# SerialTrainSensor_drill.net
KiCad netlist of a schematic drawn in EAGLE
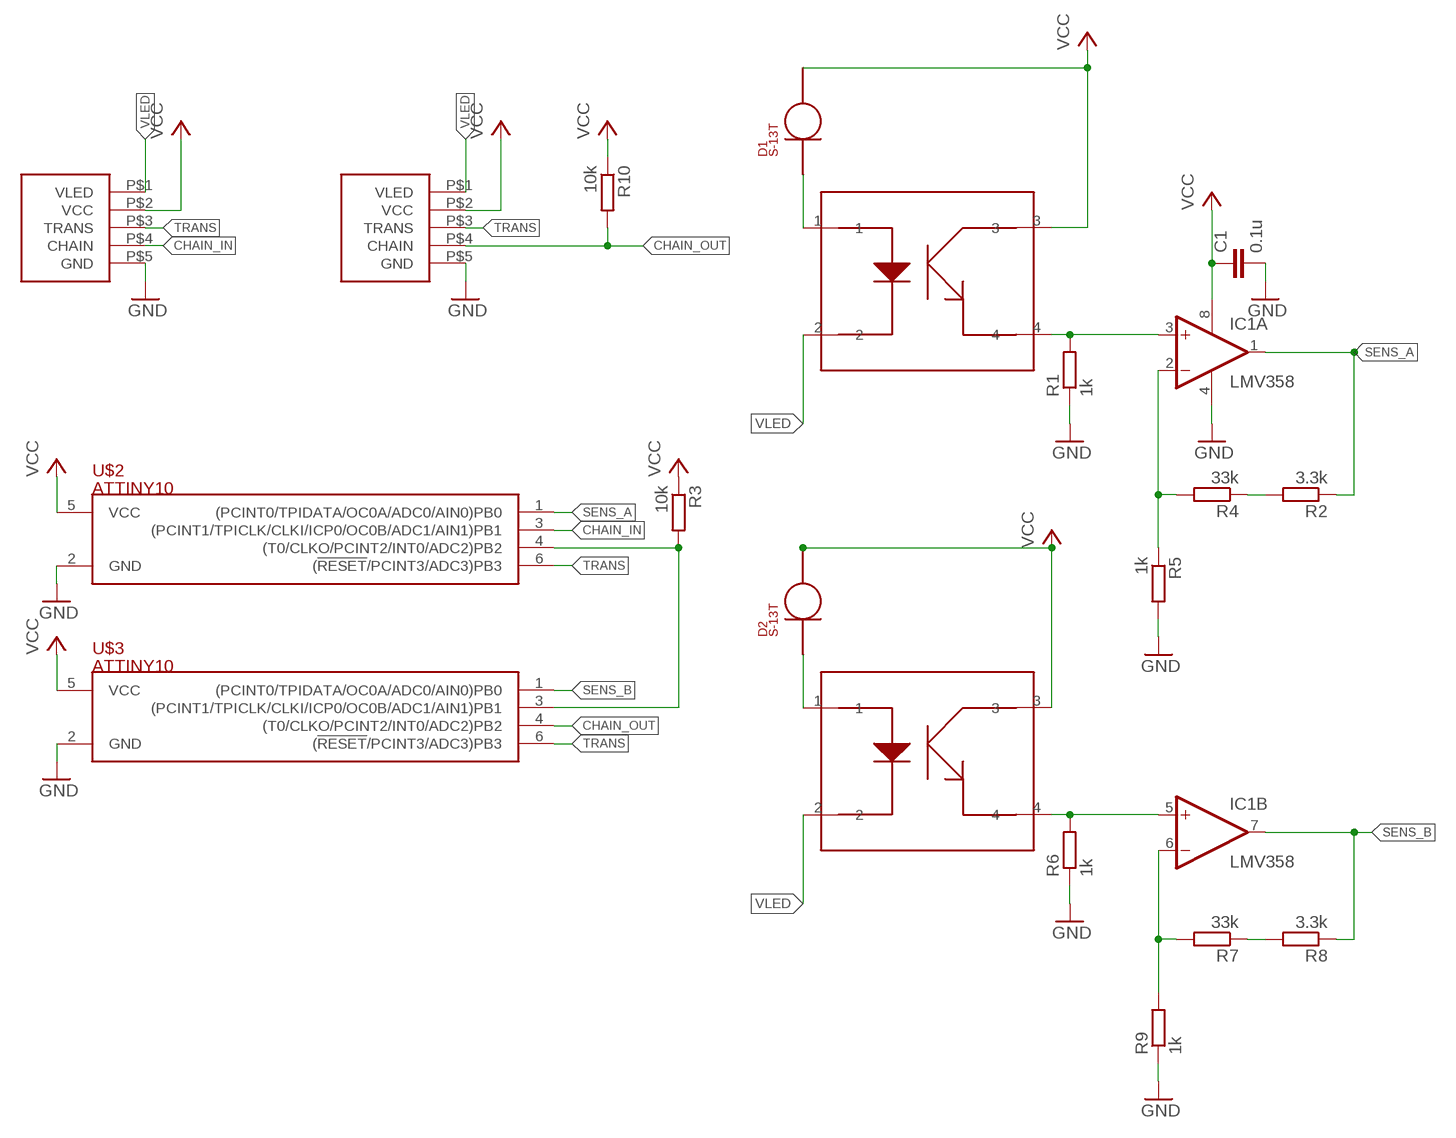
[diagram p0: schematic, sheet 1]

(export (version "E")
  (design (tool "Eeschema 10.0.6"))
  (components
    (comp (ref "C1")
      (value "0.1u")
      (footprint "eagle-import:C0603")
      (libsource (lib "eagle-import") (part "C-EUC0603"))
    )
    (comp (ref "D1")
      (value "S-13T")
      (footprint "eagle-import:S-1_3T")
      (libsource (lib "eagle-import") (part "S-13T"))
    )
    (comp (ref "D2")
      (value "S-13T")
      (footprint "eagle-import:S-1_3T")
      (libsource (lib "eagle-import") (part "S-13T"))
    )
    (comp (ref "IC1")
      (value "LMV358")
      (footprint "eagle-import:TSSOP8")
      (libsource (lib "eagle-import") (part "LMV358?"))
    )
    (comp (ref "R1")
      (value "1k")
      (footprint "eagle-import:R0603")
      (libsource (lib "eagle-import") (part "R-EU_R0603"))
    )
    (comp (ref "R2")
      (value "3.3k")
      (footprint "eagle-import:R0603")
      (libsource (lib "eagle-import") (part "R-EU_R0603"))
    )
    (comp (ref "R3")
      (value "10k")
      (footprint "eagle-import:R0603")
      (libsource (lib "eagle-import") (part "R-EU_R0603"))
    )
    (comp (ref "R4")
      (value "33k")
      (footprint "eagle-import:R0603")
      (libsource (lib "eagle-import") (part "R-EU_R0603"))
    )
    (comp (ref "R5")
      (value "1k")
      (footprint "eagle-import:R0603")
      (libsource (lib "eagle-import") (part "R-EU_R0603"))
    )
    (comp (ref "R6")
      (value "1k")
      (footprint "eagle-import:R0603")
      (libsource (lib "eagle-import") (part "R-EU_R0603"))
    )
    (comp (ref "R7")
      (value "33k")
      (footprint "eagle-import:R0603")
      (libsource (lib "eagle-import") (part "R-EU_R0603"))
    )
    (comp (ref "R8")
      (value "3.3k")
      (footprint "eagle-import:R0603")
      (libsource (lib "eagle-import") (part "R-EU_R0603"))
    )
    (comp (ref "R9")
      (value "1k")
      (footprint "eagle-import:R0603")
      (libsource (lib "eagle-import") (part "R-EU_R0603"))
    )
    (comp (ref "R10")
      (value "10k")
      (footprint "eagle-import:R0603")
      (libsource (lib "eagle-import") (part "R-EU_R0603"))
    )
    (comp (ref "SMD1")
      (value "SERIAL_SENSORHALF")
      (footprint "eagle-import:SERIAL_5_HALF")
      (libsource (lib "eagle-import") (part "SERIAL_SENSORHALF"))
    )
    (comp (ref "SMD2")
      (value "SERIAL_SENSORHALF")
      (footprint "eagle-import:SERIAL_5_HALF")
      (libsource (lib "eagle-import") (part "SERIAL_SENSORHALF"))
    )
    (comp (ref "U$1")
      (value "TPR-105F")
      (footprint "eagle-import:TPR-105F")
      (libsource (lib "eagle-import") (part "TPR-105F"))
    )
    (comp (ref "U$2")
      (value "ATTINY10")
      (footprint "eagle-import:SOT-23")
      (libsource (lib "eagle-import") (part "ATTINY10"))
    )
    (comp (ref "U$3")
      (value "ATTINY10")
      (footprint "eagle-import:SOT-23")
      (libsource (lib "eagle-import") (part "ATTINY10"))
    )
    (comp (ref "U$4")
      (value "TPR-105F")
      (footprint "eagle-import:TPR-105F")
      (libsource (lib "eagle-import") (part "TPR-105F"))
    )
  )
  (nets
    (net (code "1") (name "CHAIN_IN") (class "Default")
      (node (ref "SMD1") (pin "P$4") (pinfunction "CHAIN_P$4") (pintype "bidirectional"))
      (node (ref "U$2") (pin "3") (pinfunction "(PCINT1/TPICLK/CLKI/ICP0/OC0B/ADC1/AIN1)PB1_3") (pintype "bidirectional"))
    )
    (net (code "2") (name "CHAIN_OUT") (class "Default")
      (node (ref "R10") (pin "2") (pinfunction "2_2") (pintype "passive"))
      (node (ref "SMD2") (pin "P$4") (pinfunction "CHAIN_P$4") (pintype "bidirectional"))
      (node (ref "U$3") (pin "4") (pinfunction "(T0/CLKO/PCINT2/INT0/ADC2)PB2_4") (pintype "bidirectional"))
    )
    (net (code "3") (name "GND") (class "Default")
      (node (ref "C1") (pin "2") (pinfunction "2_2") (pintype "passive"))
      (node (ref "IC1") (pin "4") (pinfunction "V-_4") (pintype "power_in"))
      (node (ref "R1") (pin "1") (pinfunction "1_1") (pintype "passive"))
      (node (ref "R5") (pin "2") (pinfunction "2_2") (pintype "passive"))
      (node (ref "R6") (pin "1") (pinfunction "1_1") (pintype "passive"))
      (node (ref "R9") (pin "1") (pinfunction "1_1") (pintype "passive"))
      (node (ref "SMD1") (pin "P$5") (pinfunction "GND_P$5") (pintype "bidirectional"))
      (node (ref "SMD2") (pin "P$5") (pinfunction "GND_P$5") (pintype "bidirectional"))
      (node (ref "U$2") (pin "2") (pinfunction "GND_2") (pintype "power_in"))
      (node (ref "U$3") (pin "2") (pinfunction "GND_2") (pintype "power_in"))
    )
    (net (code "4") (name "Net-(D1-PadC)") (class "Default")
      (node (ref "D1") (pin "C") (pinfunction "C_C") (pintype "bidirectional"))
      (node (ref "U$1") (pin "1") (pinfunction "1_1") (pintype "bidirectional"))
    )
    (net (code "5") (name "Net-(D2-PadC)") (class "Default")
      (node (ref "D2") (pin "C") (pinfunction "C_C") (pintype "bidirectional"))
      (node (ref "U$4") (pin "1") (pinfunction "1_1") (pintype "bidirectional"))
    )
    (net (code "6") (name "Net-(IC1A-+IN)") (class "Default")
      (node (ref "IC1") (pin "3") (pinfunction "+IN_3") (pintype "input"))
      (node (ref "R1") (pin "2") (pinfunction "2_2") (pintype "passive"))
      (node (ref "U$1") (pin "4") (pinfunction "4_4") (pintype "bidirectional"))
    )
    (net (code "7") (name "Net-(IC1A--IN)") (class "Default")
      (node (ref "IC1") (pin "2") (pinfunction "-IN_2") (pintype "input"))
      (node (ref "R4") (pin "2") (pinfunction "2_2") (pintype "passive"))
      (node (ref "R5") (pin "1") (pinfunction "1_1") (pintype "passive"))
    )
    (net (code "8") (name "Net-(IC1B-+IN)") (class "Default")
      (node (ref "IC1") (pin "5") (pinfunction "+IN_5") (pintype "input"))
      (node (ref "R6") (pin "2") (pinfunction "2_2") (pintype "passive"))
      (node (ref "U$4") (pin "4") (pinfunction "4_4") (pintype "bidirectional"))
    )
    (net (code "9") (name "Net-(IC1B--IN)") (class "Default")
      (node (ref "IC1") (pin "6") (pinfunction "-IN_6") (pintype "input"))
      (node (ref "R7") (pin "2") (pinfunction "2_2") (pintype "passive"))
      (node (ref "R9") (pin "2") (pinfunction "2_2") (pintype "passive"))
    )
    (net (code "10") (name "Net-(R2-Pad2)") (class "Default")
      (node (ref "R2") (pin "2") (pinfunction "2_2") (pintype "passive"))
      (node (ref "R4") (pin "1") (pinfunction "1_1") (pintype "passive"))
    )
    (net (code "11") (name "Net-(R7-Pad1)") (class "Default")
      (node (ref "R7") (pin "1") (pinfunction "1_1") (pintype "passive"))
      (node (ref "R8") (pin "2") (pinfunction "2_2") (pintype "passive"))
    )
    (net (code "12") (name "Net-(U$2-(T0{slash}CLKO{slash}PCINT2{slash}INT0{slash}ADC2)PB2)") (class "Default")
      (node (ref "R3") (pin "2") (pinfunction "2_2") (pintype "passive"))
      (node (ref "U$2") (pin "4") (pinfunction "(T0/CLKO/PCINT2/INT0/ADC2)PB2_4") (pintype "bidirectional"))
      (node (ref "U$3") (pin "3") (pinfunction "(PCINT1/TPICLK/CLKI/ICP0/OC0B/ADC1/AIN1)PB1_3") (pintype "bidirectional"))
    )
    (net (code "13") (name "SENS_A") (class "Default")
      (node (ref "IC1") (pin "1") (pinfunction "OUT_1") (pintype "output"))
      (node (ref "R2") (pin "1") (pinfunction "1_1") (pintype "passive"))
      (node (ref "U$2") (pin "1") (pinfunction "(PCINT0/TPIDATA/OC0A/ADC0/AIN0)PB0_1") (pintype "bidirectional"))
    )
    (net (code "14") (name "SENS_B") (class "Default")
      (node (ref "IC1") (pin "7") (pinfunction "OUT_7") (pintype "output"))
      (node (ref "R8") (pin "1") (pinfunction "1_1") (pintype "passive"))
      (node (ref "U$3") (pin "1") (pinfunction "(PCINT0/TPIDATA/OC0A/ADC0/AIN0)PB0_1") (pintype "bidirectional"))
    )
    (net (code "15") (name "TRANS") (class "Default")
      (node (ref "SMD1") (pin "P$3") (pinfunction "TRANS_P$3") (pintype "bidirectional"))
      (node (ref "SMD2") (pin "P$3") (pinfunction "TRANS_P$3") (pintype "bidirectional"))
      (node (ref "U$2") (pin "6") (pinfunction "(~{RESET}/PCINT3/ADC3)PB3_6") (pintype "bidirectional"))
      (node (ref "U$3") (pin "6") (pinfunction "(~{RESET}/PCINT3/ADC3)PB3_6") (pintype "bidirectional"))
    )
    (net (code "16") (name "VCC") (class "Default")
      (node (ref "C1") (pin "1") (pinfunction "1_1") (pintype "passive"))
      (node (ref "D1") (pin "A") (pinfunction "A_A") (pintype "bidirectional"))
      (node (ref "D2") (pin "A") (pinfunction "A_A") (pintype "bidirectional"))
      (node (ref "IC1") (pin "8") (pinfunction "V+_8") (pintype "power_in"))
      (node (ref "R10") (pin "1") (pinfunction "1_1") (pintype "passive"))
      (node (ref "R3") (pin "1") (pinfunction "1_1") (pintype "passive"))
      (node (ref "SMD1") (pin "P$2") (pinfunction "VCC_P$2") (pintype "bidirectional"))
      (node (ref "SMD2") (pin "P$2") (pinfunction "VCC_P$2") (pintype "bidirectional"))
      (node (ref "U$1") (pin "3") (pinfunction "3_3") (pintype "bidirectional"))
      (node (ref "U$2") (pin "5") (pinfunction "VCC_5") (pintype "power_in"))
      (node (ref "U$3") (pin "5") (pinfunction "VCC_5") (pintype "power_in"))
      (node (ref "U$4") (pin "3") (pinfunction "3_3") (pintype "bidirectional"))
    )
    (net (code "17") (name "VLED") (class "Default")
      (node (ref "SMD1") (pin "P$1") (pinfunction "VLED_P$1") (pintype "bidirectional"))
      (node (ref "SMD2") (pin "P$1") (pinfunction "VLED_P$1") (pintype "bidirectional"))
      (node (ref "U$1") (pin "2") (pinfunction "2_2") (pintype "bidirectional"))
      (node (ref "U$4") (pin "2") (pinfunction "2_2") (pintype "bidirectional"))
    )
  )
)
